# p8_led_matrix.net
KiCad netlist of a schematic drawn in Altium Designer
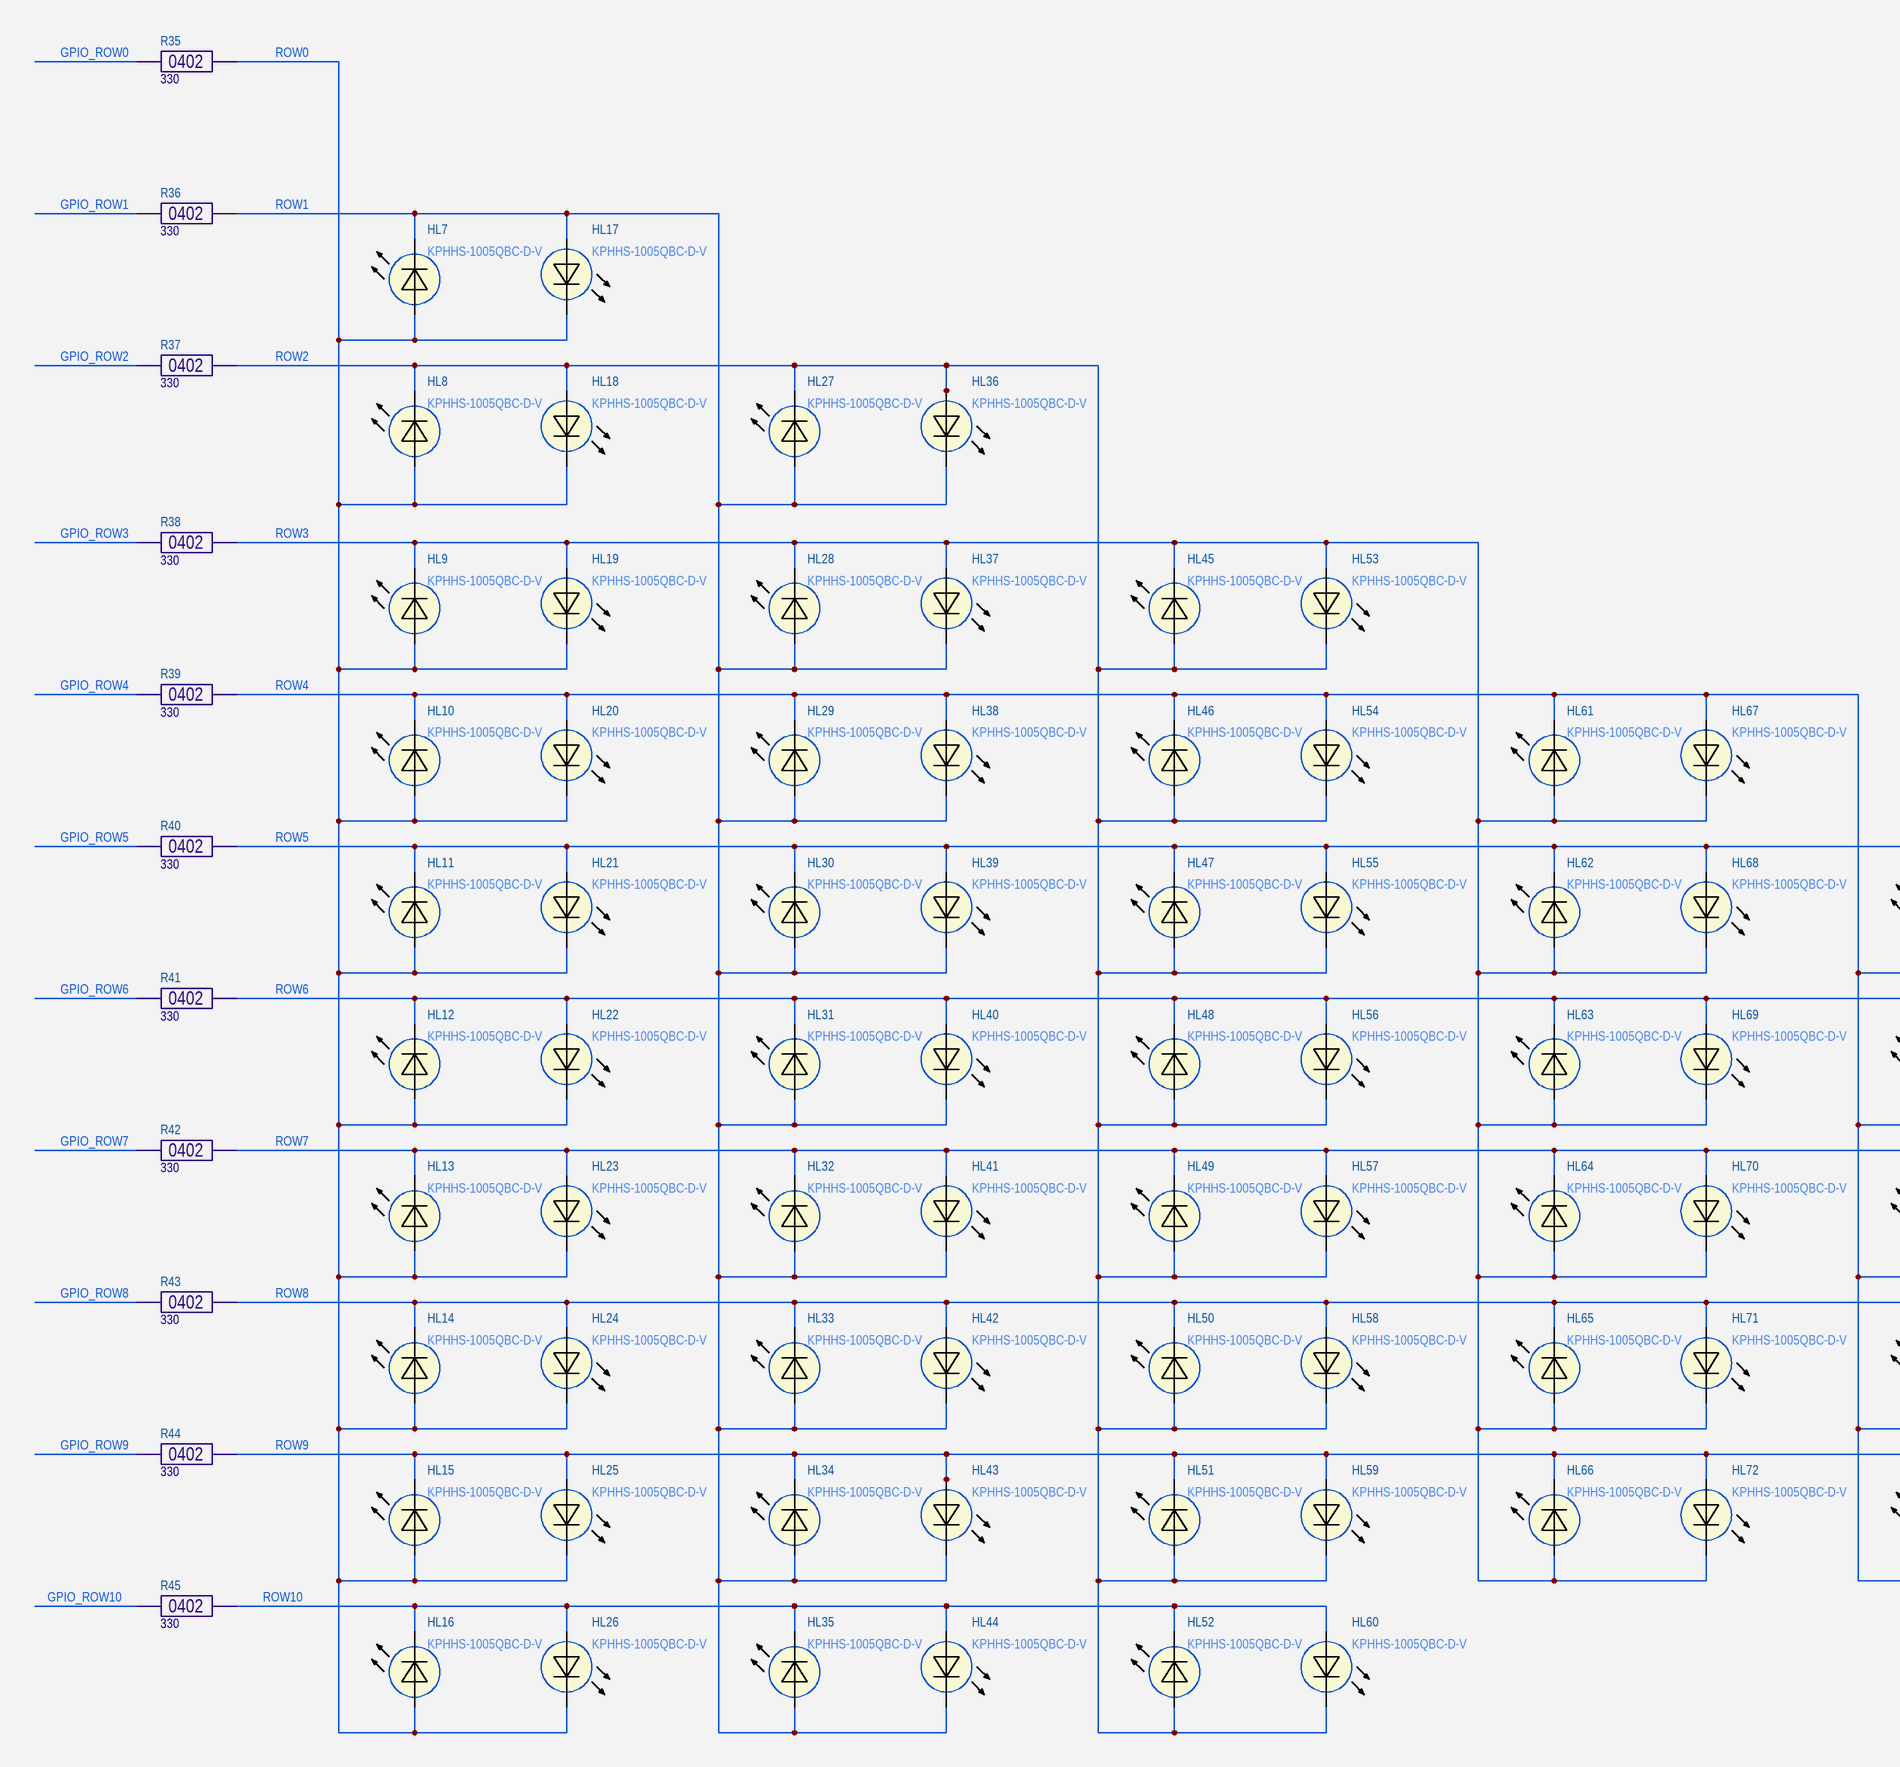
[diagram p0: p8_led_matrix.SchDoc, left]
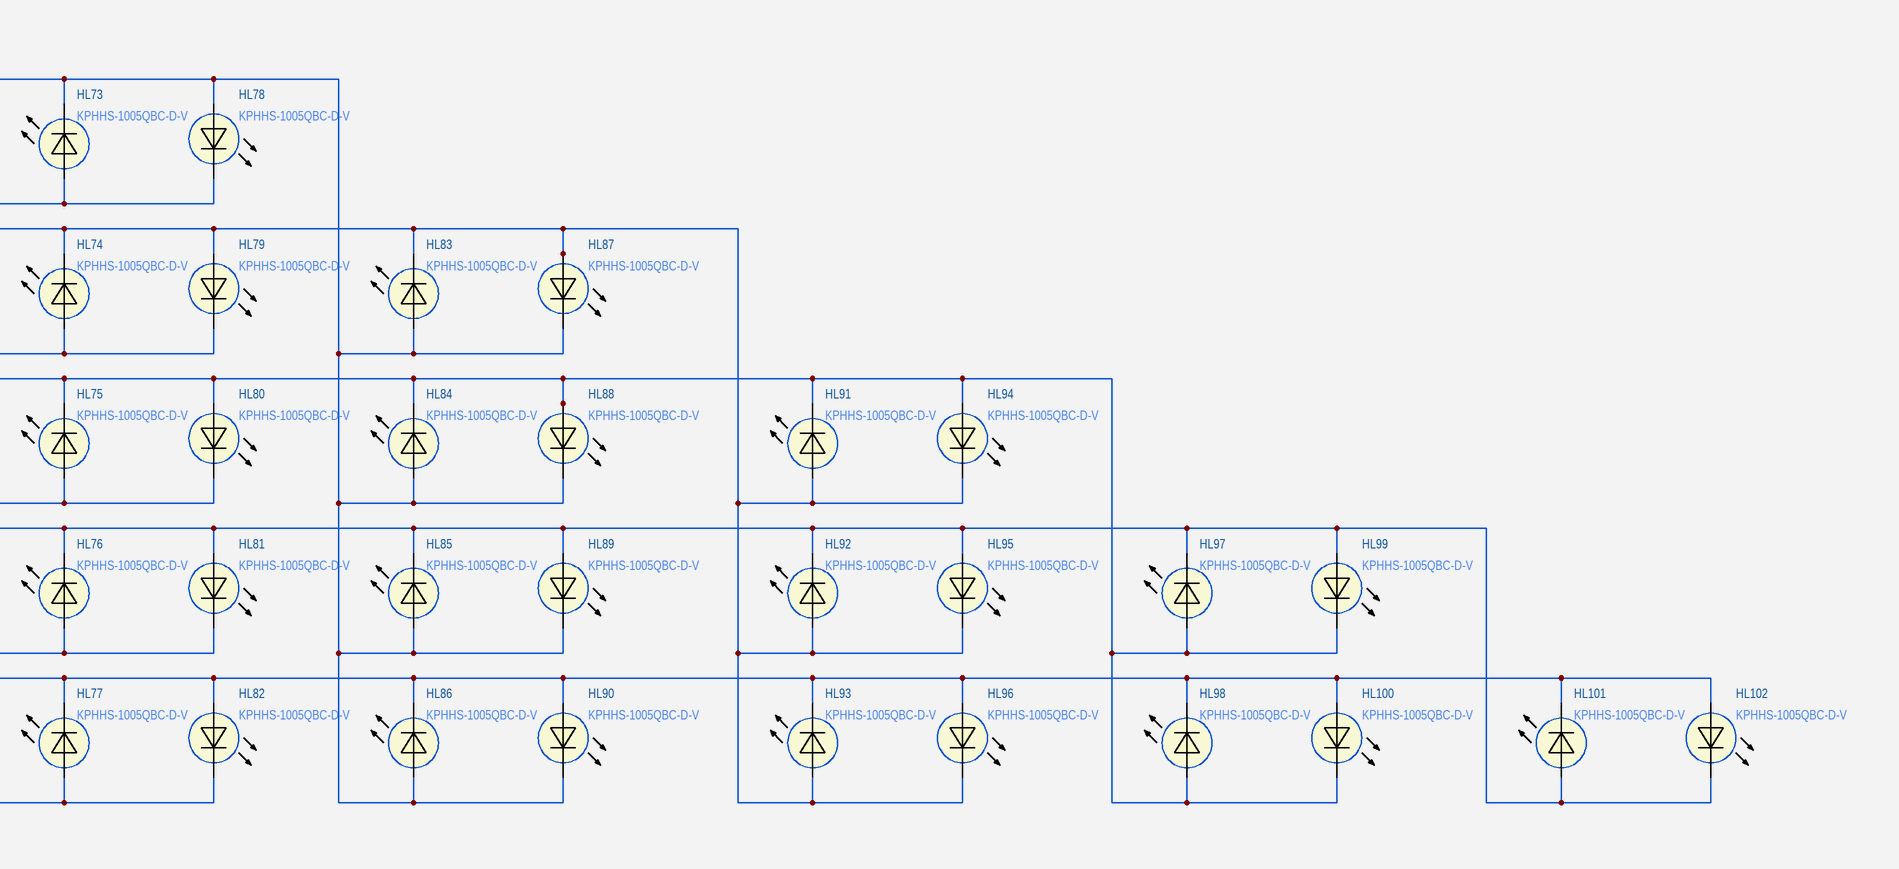
[diagram p1: p8_led_matrix.SchDoc, right]

(export (version "E")
  (design (tool "Eeschema 10.0.6"))
  (components
    (comp (ref "HL7")
      (value "KPHHS-1005QBC-D-V")
      (footprint "PcbLib_Others:LED0402B")
      (description "Blue led (package case 0402)")
      (fields (field (name "MANUFACTURER") "Kingbright Company LLC."))
      (libsource (lib "Schlib_Kingbright") (part "KPHHS-1005QBC-D-V"))
    )
    (comp (ref "HL8")
      (value "KPHHS-1005QBC-D-V")
      (footprint "PcbLib_Others:LED0402B")
      (description "Blue led (package case 0402)")
      (fields (field (name "MANUFACTURER") "Kingbright Company LLC."))
      (libsource (lib "Schlib_Kingbright") (part "KPHHS-1005QBC-D-V"))
    )
    (comp (ref "HL9")
      (value "KPHHS-1005QBC-D-V")
      (footprint "PcbLib_Others:LED0402B")
      (description "Blue led (package case 0402)")
      (fields (field (name "MANUFACTURER") "Kingbright Company LLC."))
      (libsource (lib "Schlib_Kingbright") (part "KPHHS-1005QBC-D-V"))
    )
    (comp (ref "HL10")
      (value "KPHHS-1005QBC-D-V")
      (footprint "PcbLib_Others:LED0402B")
      (description "Blue led (package case 0402)")
      (fields (field (name "MANUFACTURER") "Kingbright Company LLC."))
      (libsource (lib "Schlib_Kingbright") (part "KPHHS-1005QBC-D-V"))
    )
    (comp (ref "HL11")
      (value "KPHHS-1005QBC-D-V")
      (footprint "PcbLib_Others:LED0402B")
      (description "Blue led (package case 0402)")
      (fields (field (name "MANUFACTURER") "Kingbright Company LLC."))
      (libsource (lib "Schlib_Kingbright") (part "KPHHS-1005QBC-D-V"))
    )
    (comp (ref "HL12")
      (value "KPHHS-1005QBC-D-V")
      (footprint "PcbLib_Others:LED0402B")
      (description "Blue led (package case 0402)")
      (fields (field (name "MANUFACTURER") "Kingbright Company LLC."))
      (libsource (lib "Schlib_Kingbright") (part "KPHHS-1005QBC-D-V"))
    )
    (comp (ref "HL13")
      (value "KPHHS-1005QBC-D-V")
      (footprint "PcbLib_Others:LED0402B")
      (description "Blue led (package case 0402)")
      (fields (field (name "MANUFACTURER") "Kingbright Company LLC."))
      (libsource (lib "Schlib_Kingbright") (part "KPHHS-1005QBC-D-V"))
    )
    (comp (ref "HL14")
      (value "KPHHS-1005QBC-D-V")
      (footprint "PcbLib_Others:LED0402B")
      (description "Blue led (package case 0402)")
      (fields (field (name "MANUFACTURER") "Kingbright Company LLC."))
      (libsource (lib "Schlib_Kingbright") (part "KPHHS-1005QBC-D-V"))
    )
    (comp (ref "HL15")
      (value "KPHHS-1005QBC-D-V")
      (footprint "PcbLib_Others:LED0402B")
      (description "Blue led (package case 0402)")
      (fields (field (name "MANUFACTURER") "Kingbright Company LLC."))
      (libsource (lib "Schlib_Kingbright") (part "KPHHS-1005QBC-D-V"))
    )
    (comp (ref "HL16")
      (value "KPHHS-1005QBC-D-V")
      (footprint "PcbLib_Others:LED0402B")
      (description "Blue led (package case 0402)")
      (fields (field (name "MANUFACTURER") "Kingbright Company LLC."))
      (libsource (lib "Schlib_Kingbright") (part "KPHHS-1005QBC-D-V"))
    )
    (comp (ref "HL17")
      (value "KPHHS-1005QBC-D-V")
      (footprint "PcbLib_Others:LED0402B")
      (description "Blue led (package case 0402)")
      (fields (field (name "MANUFACTURER") "Kingbright Company LLC."))
      (libsource (lib "Schlib_Kingbright") (part "KPHHS-1005QBC-D-V"))
    )
    (comp (ref "HL18")
      (value "KPHHS-1005QBC-D-V")
      (footprint "PcbLib_Others:LED0402B")
      (description "Blue led (package case 0402)")
      (fields (field (name "MANUFACTURER") "Kingbright Company LLC."))
      (libsource (lib "Schlib_Kingbright") (part "KPHHS-1005QBC-D-V"))
    )
    (comp (ref "HL19")
      (value "KPHHS-1005QBC-D-V")
      (footprint "PcbLib_Others:LED0402B")
      (description "Blue led (package case 0402)")
      (fields (field (name "MANUFACTURER") "Kingbright Company LLC."))
      (libsource (lib "Schlib_Kingbright") (part "KPHHS-1005QBC-D-V"))
    )
    (comp (ref "HL20")
      (value "KPHHS-1005QBC-D-V")
      (footprint "PcbLib_Others:LED0402B")
      (description "Blue led (package case 0402)")
      (fields (field (name "MANUFACTURER") "Kingbright Company LLC."))
      (libsource (lib "Schlib_Kingbright") (part "KPHHS-1005QBC-D-V"))
    )
    (comp (ref "HL21")
      (value "KPHHS-1005QBC-D-V")
      (footprint "PcbLib_Others:LED0402B")
      (description "Blue led (package case 0402)")
      (fields (field (name "MANUFACTURER") "Kingbright Company LLC."))
      (libsource (lib "Schlib_Kingbright") (part "KPHHS-1005QBC-D-V"))
    )
    (comp (ref "HL22")
      (value "KPHHS-1005QBC-D-V")
      (footprint "PcbLib_Others:LED0402B")
      (description "Blue led (package case 0402)")
      (fields (field (name "MANUFACTURER") "Kingbright Company LLC."))
      (libsource (lib "Schlib_Kingbright") (part "KPHHS-1005QBC-D-V"))
    )
    (comp (ref "HL23")
      (value "KPHHS-1005QBC-D-V")
      (footprint "PcbLib_Others:LED0402B")
      (description "Blue led (package case 0402)")
      (fields (field (name "MANUFACTURER") "Kingbright Company LLC."))
      (libsource (lib "Schlib_Kingbright") (part "KPHHS-1005QBC-D-V"))
    )
    (comp (ref "HL24")
      (value "KPHHS-1005QBC-D-V")
      (footprint "PcbLib_Others:LED0402B")
      (description "Blue led (package case 0402)")
      (fields (field (name "MANUFACTURER") "Kingbright Company LLC."))
      (libsource (lib "Schlib_Kingbright") (part "KPHHS-1005QBC-D-V"))
    )
    (comp (ref "HL25")
      (value "KPHHS-1005QBC-D-V")
      (footprint "PcbLib_Others:LED0402B")
      (description "Blue led (package case 0402)")
      (fields (field (name "MANUFACTURER") "Kingbright Company LLC."))
      (libsource (lib "Schlib_Kingbright") (part "KPHHS-1005QBC-D-V"))
    )
    (comp (ref "HL26")
      (value "KPHHS-1005QBC-D-V")
      (footprint "PcbLib_Others:LED0402B")
      (description "Blue led (package case 0402)")
      (fields (field (name "MANUFACTURER") "Kingbright Company LLC."))
      (libsource (lib "Schlib_Kingbright") (part "KPHHS-1005QBC-D-V"))
    )
    (comp (ref "HL27")
      (value "KPHHS-1005QBC-D-V")
      (footprint "PcbLib_Others:LED0402B")
      (description "Blue led (package case 0402)")
      (fields (field (name "MANUFACTURER") "Kingbright Company LLC."))
      (libsource (lib "Schlib_Kingbright") (part "KPHHS-1005QBC-D-V"))
    )
    (comp (ref "HL28")
      (value "KPHHS-1005QBC-D-V")
      (footprint "PcbLib_Others:LED0402B")
      (description "Blue led (package case 0402)")
      (fields (field (name "MANUFACTURER") "Kingbright Company LLC."))
      (libsource (lib "Schlib_Kingbright") (part "KPHHS-1005QBC-D-V"))
    )
    (comp (ref "HL29")
      (value "KPHHS-1005QBC-D-V")
      (footprint "PcbLib_Others:LED0402B")
      (description "Blue led (package case 0402)")
      (fields (field (name "MANUFACTURER") "Kingbright Company LLC."))
      (libsource (lib "Schlib_Kingbright") (part "KPHHS-1005QBC-D-V"))
    )
    (comp (ref "HL30")
      (value "KPHHS-1005QBC-D-V")
      (footprint "PcbLib_Others:LED0402B")
      (description "Blue led (package case 0402)")
      (fields (field (name "MANUFACTURER") "Kingbright Company LLC."))
      (libsource (lib "Schlib_Kingbright") (part "KPHHS-1005QBC-D-V"))
    )
    (comp (ref "HL31")
      (value "KPHHS-1005QBC-D-V")
      (footprint "PcbLib_Others:LED0402B")
      (description "Blue led (package case 0402)")
      (fields (field (name "MANUFACTURER") "Kingbright Company LLC."))
      (libsource (lib "Schlib_Kingbright") (part "KPHHS-1005QBC-D-V"))
    )
    (comp (ref "HL32")
      (value "KPHHS-1005QBC-D-V")
      (footprint "PcbLib_Others:LED0402B")
      (description "Blue led (package case 0402)")
      (fields (field (name "MANUFACTURER") "Kingbright Company LLC."))
      (libsource (lib "Schlib_Kingbright") (part "KPHHS-1005QBC-D-V"))
    )
    (comp (ref "HL33")
      (value "KPHHS-1005QBC-D-V")
      (footprint "PcbLib_Others:LED0402B")
      (description "Blue led (package case 0402)")
      (fields (field (name "MANUFACTURER") "Kingbright Company LLC."))
      (libsource (lib "Schlib_Kingbright") (part "KPHHS-1005QBC-D-V"))
    )
    (comp (ref "HL34")
      (value "KPHHS-1005QBC-D-V")
      (footprint "PcbLib_Others:LED0402B")
      (description "Blue led (package case 0402)")
      (fields (field (name "MANUFACTURER") "Kingbright Company LLC."))
      (libsource (lib "Schlib_Kingbright") (part "KPHHS-1005QBC-D-V"))
    )
    (comp (ref "HL35")
      (value "KPHHS-1005QBC-D-V")
      (footprint "PcbLib_Others:LED0402B")
      (description "Blue led (package case 0402)")
      (fields (field (name "MANUFACTURER") "Kingbright Company LLC."))
      (libsource (lib "Schlib_Kingbright") (part "KPHHS-1005QBC-D-V"))
    )
    (comp (ref "HL36")
      (value "KPHHS-1005QBC-D-V")
      (footprint "PcbLib_Others:LED0402B")
      (description "Blue led (package case 0402)")
      (fields (field (name "MANUFACTURER") "Kingbright Company LLC."))
      (libsource (lib "Schlib_Kingbright") (part "KPHHS-1005QBC-D-V"))
    )
    (comp (ref "HL37")
      (value "KPHHS-1005QBC-D-V")
      (footprint "PcbLib_Others:LED0402B")
      (description "Blue led (package case 0402)")
      (fields (field (name "MANUFACTURER") "Kingbright Company LLC."))
      (libsource (lib "Schlib_Kingbright") (part "KPHHS-1005QBC-D-V"))
    )
    (comp (ref "HL38")
      (value "KPHHS-1005QBC-D-V")
      (footprint "PcbLib_Others:LED0402B")
      (description "Blue led (package case 0402)")
      (fields (field (name "MANUFACTURER") "Kingbright Company LLC."))
      (libsource (lib "Schlib_Kingbright") (part "KPHHS-1005QBC-D-V"))
    )
    (comp (ref "HL39")
      (value "KPHHS-1005QBC-D-V")
      (footprint "PcbLib_Others:LED0402B")
      (description "Blue led (package case 0402)")
      (fields (field (name "MANUFACTURER") "Kingbright Company LLC."))
      (libsource (lib "Schlib_Kingbright") (part "KPHHS-1005QBC-D-V"))
    )
    (comp (ref "HL40")
      (value "KPHHS-1005QBC-D-V")
      (footprint "PcbLib_Others:LED0402B")
      (description "Blue led (package case 0402)")
      (fields (field (name "MANUFACTURER") "Kingbright Company LLC."))
      (libsource (lib "Schlib_Kingbright") (part "KPHHS-1005QBC-D-V"))
    )
    (comp (ref "HL41")
      (value "KPHHS-1005QBC-D-V")
      (footprint "PcbLib_Others:LED0402B")
      (description "Blue led (package case 0402)")
      (fields (field (name "MANUFACTURER") "Kingbright Company LLC."))
      (libsource (lib "Schlib_Kingbright") (part "KPHHS-1005QBC-D-V"))
    )
    (comp (ref "HL42")
      (value "KPHHS-1005QBC-D-V")
      (footprint "PcbLib_Others:LED0402B")
      (description "Blue led (package case 0402)")
      (fields (field (name "MANUFACTURER") "Kingbright Company LLC."))
      (libsource (lib "Schlib_Kingbright") (part "KPHHS-1005QBC-D-V"))
    )
    (comp (ref "HL43")
      (value "KPHHS-1005QBC-D-V")
      (footprint "PcbLib_Others:LED0402B")
      (description "Blue led (package case 0402)")
      (fields (field (name "MANUFACTURER") "Kingbright Company LLC."))
      (libsource (lib "Schlib_Kingbright") (part "KPHHS-1005QBC-D-V"))
    )
    (comp (ref "HL44")
      (value "KPHHS-1005QBC-D-V")
      (footprint "PcbLib_Others:LED0402B")
      (description "Blue led (package case 0402)")
      (fields (field (name "MANUFACTURER") "Kingbright Company LLC."))
      (libsource (lib "Schlib_Kingbright") (part "KPHHS-1005QBC-D-V"))
    )
    (comp (ref "HL45")
      (value "KPHHS-1005QBC-D-V")
      (footprint "PcbLib_Others:LED0402B")
      (description "Blue led (package case 0402)")
      (fields (field (name "MANUFACTURER") "Kingbright Company LLC."))
      (libsource (lib "Schlib_Kingbright") (part "KPHHS-1005QBC-D-V"))
    )
    (comp (ref "HL46")
      (value "KPHHS-1005QBC-D-V")
      (footprint "PcbLib_Others:LED0402B")
      (description "Blue led (package case 0402)")
      (fields (field (name "MANUFACTURER") "Kingbright Company LLC."))
      (libsource (lib "Schlib_Kingbright") (part "KPHHS-1005QBC-D-V"))
    )
    (comp (ref "HL47")
      (value "KPHHS-1005QBC-D-V")
      (footprint "PcbLib_Others:LED0402B")
      (description "Blue led (package case 0402)")
      (fields (field (name "MANUFACTURER") "Kingbright Company LLC."))
      (libsource (lib "Schlib_Kingbright") (part "KPHHS-1005QBC-D-V"))
    )
    (comp (ref "HL48")
      (value "KPHHS-1005QBC-D-V")
      (footprint "PcbLib_Others:LED0402B")
      (description "Blue led (package case 0402)")
      (fields (field (name "MANUFACTURER") "Kingbright Company LLC."))
      (libsource (lib "Schlib_Kingbright") (part "KPHHS-1005QBC-D-V"))
    )
    (comp (ref "HL49")
      (value "KPHHS-1005QBC-D-V")
      (footprint "PcbLib_Others:LED0402B")
      (description "Blue led (package case 0402)")
      (fields (field (name "MANUFACTURER") "Kingbright Company LLC."))
      (libsource (lib "Schlib_Kingbright") (part "KPHHS-1005QBC-D-V"))
    )
    (comp (ref "HL50")
      (value "KPHHS-1005QBC-D-V")
      (footprint "PcbLib_Others:LED0402B")
      (description "Blue led (package case 0402)")
      (fields (field (name "MANUFACTURER") "Kingbright Company LLC."))
      (libsource (lib "Schlib_Kingbright") (part "KPHHS-1005QBC-D-V"))
    )
    (comp (ref "HL51")
      (value "KPHHS-1005QBC-D-V")
      (footprint "PcbLib_Others:LED0402B")
      (description "Blue led (package case 0402)")
      (fields (field (name "MANUFACTURER") "Kingbright Company LLC."))
      (libsource (lib "Schlib_Kingbright") (part "KPHHS-1005QBC-D-V"))
    )
    (comp (ref "HL52")
      (value "KPHHS-1005QBC-D-V")
      (footprint "PcbLib_Others:LED0402B")
      (description "Blue led (package case 0402)")
      (fields (field (name "MANUFACTURER") "Kingbright Company LLC."))
      (libsource (lib "Schlib_Kingbright") (part "KPHHS-1005QBC-D-V"))
    )
    (comp (ref "HL53")
      (value "KPHHS-1005QBC-D-V")
      (footprint "PcbLib_Others:LED0402B")
      (description "Blue led (package case 0402)")
      (fields (field (name "MANUFACTURER") "Kingbright Company LLC."))
      (libsource (lib "Schlib_Kingbright") (part "KPHHS-1005QBC-D-V"))
    )
    (comp (ref "HL54")
      (value "KPHHS-1005QBC-D-V")
      (footprint "PcbLib_Others:LED0402B")
      (description "Blue led (package case 0402)")
      (fields (field (name "MANUFACTURER") "Kingbright Company LLC."))
      (libsource (lib "Schlib_Kingbright") (part "KPHHS-1005QBC-D-V"))
    )
    (comp (ref "HL55")
      (value "KPHHS-1005QBC-D-V")
      (footprint "PcbLib_Others:LED0402B")
      (description "Blue led (package case 0402)")
      (fields (field (name "MANUFACTURER") "Kingbright Company LLC."))
      (libsource (lib "Schlib_Kingbright") (part "KPHHS-1005QBC-D-V"))
    )
    (comp (ref "HL56")
      (value "KPHHS-1005QBC-D-V")
      (footprint "PcbLib_Others:LED0402B")
      (description "Blue led (package case 0402)")
      (fields (field (name "MANUFACTURER") "Kingbright Company LLC."))
      (libsource (lib "Schlib_Kingbright") (part "KPHHS-1005QBC-D-V"))
    )
    (comp (ref "HL57")
      (value "KPHHS-1005QBC-D-V")
      (footprint "PcbLib_Others:LED0402B")
      (description "Blue led (package case 0402)")
      (fields (field (name "MANUFACTURER") "Kingbright Company LLC."))
      (libsource (lib "Schlib_Kingbright") (part "KPHHS-1005QBC-D-V"))
    )
    (comp (ref "HL58")
      (value "KPHHS-1005QBC-D-V")
      (footprint "PcbLib_Others:LED0402B")
      (description "Blue led (package case 0402)")
      (fields (field (name "MANUFACTURER") "Kingbright Company LLC."))
      (libsource (lib "Schlib_Kingbright") (part "KPHHS-1005QBC-D-V"))
    )
    (comp (ref "HL59")
      (value "KPHHS-1005QBC-D-V")
      (footprint "PcbLib_Others:LED0402B")
      (description "Blue led (package case 0402)")
      (fields (field (name "MANUFACTURER") "Kingbright Company LLC."))
      (libsource (lib "Schlib_Kingbright") (part "KPHHS-1005QBC-D-V"))
    )
    (comp (ref "HL60")
      (value "KPHHS-1005QBC-D-V")
      (footprint "PcbLib_Others:LED0402B")
      (description "Blue led (package case 0402)")
      (fields (field (name "MANUFACTURER") "Kingbright Company LLC."))
      (libsource (lib "Schlib_Kingbright") (part "KPHHS-1005QBC-D-V"))
    )
    (comp (ref "HL61")
      (value "KPHHS-1005QBC-D-V")
      (footprint "PcbLib_Others:LED0402B")
      (description "Blue led (package case 0402)")
      (fields (field (name "MANUFACTURER") "Kingbright Company LLC."))
      (libsource (lib "Schlib_Kingbright") (part "KPHHS-1005QBC-D-V"))
    )
    (comp (ref "HL62")
      (value "KPHHS-1005QBC-D-V")
      (footprint "PcbLib_Others:LED0402B")
      (description "Blue led (package case 0402)")
      (fields (field (name "MANUFACTURER") "Kingbright Company LLC."))
      (libsource (lib "Schlib_Kingbright") (part "KPHHS-1005QBC-D-V"))
    )
    (comp (ref "HL63")
      (value "KPHHS-1005QBC-D-V")
      (footprint "PcbLib_Others:LED0402B")
      (description "Blue led (package case 0402)")
      (fields (field (name "MANUFACTURER") "Kingbright Company LLC."))
      (libsource (lib "Schlib_Kingbright") (part "KPHHS-1005QBC-D-V"))
    )
    (comp (ref "HL64")
      (value "KPHHS-1005QBC-D-V")
      (footprint "PcbLib_Others:LED0402B")
      (description "Blue led (package case 0402)")
      (fields (field (name "MANUFACTURER") "Kingbright Company LLC."))
      (libsource (lib "Schlib_Kingbright") (part "KPHHS-1005QBC-D-V"))
    )
    (comp (ref "HL65")
      (value "KPHHS-1005QBC-D-V")
      (footprint "PcbLib_Others:LED0402B")
      (description "Blue led (package case 0402)")
      (fields (field (name "MANUFACTURER") "Kingbright Company LLC."))
      (libsource (lib "Schlib_Kingbright") (part "KPHHS-1005QBC-D-V"))
    )
    (comp (ref "HL66")
      (value "KPHHS-1005QBC-D-V")
      (footprint "PcbLib_Others:LED0402B")
      (description "Blue led (package case 0402)")
      (fields (field (name "MANUFACTURER") "Kingbright Company LLC."))
      (libsource (lib "Schlib_Kingbright") (part "KPHHS-1005QBC-D-V"))
    )
    (comp (ref "HL67")
      (value "KPHHS-1005QBC-D-V")
      (footprint "PcbLib_Others:LED0402B")
      (description "Blue led (package case 0402)")
      (fields (field (name "MANUFACTURER") "Kingbright Company LLC."))
      (libsource (lib "Schlib_Kingbright") (part "KPHHS-1005QBC-D-V"))
    )
    (comp (ref "HL68")
      (value "KPHHS-1005QBC-D-V")
      (footprint "PcbLib_Others:LED0402B")
      (description "Blue led (package case 0402)")
      (fields (field (name "MANUFACTURER") "Kingbright Company LLC."))
      (libsource (lib "Schlib_Kingbright") (part "KPHHS-1005QBC-D-V"))
    )
    (comp (ref "HL69")
      (value "KPHHS-1005QBC-D-V")
      (footprint "PcbLib_Others:LED0402B")
      (description "Blue led (package case 0402)")
      (fields (field (name "MANUFACTURER") "Kingbright Company LLC."))
      (libsource (lib "Schlib_Kingbright") (part "KPHHS-1005QBC-D-V"))
    )
    (comp (ref "HL70")
      (value "KPHHS-1005QBC-D-V")
      (footprint "PcbLib_Others:LED0402B")
      (description "Blue led (package case 0402)")
      (fields (field (name "MANUFACTURER") "Kingbright Company LLC."))
      (libsource (lib "Schlib_Kingbright") (part "KPHHS-1005QBC-D-V"))
    )
    (comp (ref "HL71")
      (value "KPHHS-1005QBC-D-V")
      (footprint "PcbLib_Others:LED0402B")
      (description "Blue led (package case 0402)")
      (fields (field (name "MANUFACTURER") "Kingbright Company LLC."))
      (libsource (lib "Schlib_Kingbright") (part "KPHHS-1005QBC-D-V"))
    )
    (comp (ref "HL72")
      (value "KPHHS-1005QBC-D-V")
      (footprint "PcbLib_Others:LED0402B")
      (description "Blue led (package case 0402)")
      (fields (field (name "MANUFACTURER") "Kingbright Company LLC."))
      (libsource (lib "Schlib_Kingbright") (part "KPHHS-1005QBC-D-V"))
    )
    (comp (ref "HL73")
      (value "KPHHS-1005QBC-D-V")
      (footprint "PcbLib_Others:LED0402B")
      (description "Blue led (package case 0402)")
      (fields (field (name "MANUFACTURER") "Kingbright Company LLC."))
      (libsource (lib "Schlib_Kingbright") (part "KPHHS-1005QBC-D-V"))
    )
    (comp (ref "HL74")
      (value "KPHHS-1005QBC-D-V")
      (footprint "PcbLib_Others:LED0402B")
      (description "Blue led (package case 0402)")
      (fields (field (name "MANUFACTURER") "Kingbright Company LLC."))
      (libsource (lib "Schlib_Kingbright") (part "KPHHS-1005QBC-D-V"))
    )
    (comp (ref "HL75")
      (value "KPHHS-1005QBC-D-V")
      (footprint "PcbLib_Others:LED0402B")
      (description "Blue led (package case 0402)")
      (fields (field (name "MANUFACTURER") "Kingbright Company LLC."))
      (libsource (lib "Schlib_Kingbright") (part "KPHHS-1005QBC-D-V"))
    )
    (comp (ref "HL76")
      (value "KPHHS-1005QBC-D-V")
      (footprint "PcbLib_Others:LED0402B")
      (description "Blue led (package case 0402)")
      (fields (field (name "MANUFACTURER") "Kingbright Company LLC."))
      (libsource (lib "Schlib_Kingbright") (part "KPHHS-1005QBC-D-V"))
    )
    (comp (ref "HL77")
      (value "KPHHS-1005QBC-D-V")
      (footprint "PcbLib_Others:LED0402B")
      (description "Blue led (package case 0402)")
      (fields (field (name "MANUFACTURER") "Kingbright Company LLC."))
      (libsource (lib "Schlib_Kingbright") (part "KPHHS-1005QBC-D-V"))
    )
    (comp (ref "HL78")
      (value "KPHHS-1005QBC-D-V")
      (footprint "PcbLib_Others:LED0402B")
      (description "Blue led (package case 0402)")
      (fields (field (name "MANUFACTURER") "Kingbright Company LLC."))
      (libsource (lib "Schlib_Kingbright") (part "KPHHS-1005QBC-D-V"))
    )
    (comp (ref "HL79")
      (value "KPHHS-1005QBC-D-V")
      (footprint "PcbLib_Others:LED0402B")
      (description "Blue led (package case 0402)")
      (fields (field (name "MANUFACTURER") "Kingbright Company LLC."))
      (libsource (lib "Schlib_Kingbright") (part "KPHHS-1005QBC-D-V"))
    )
    (comp (ref "HL80")
      (value "KPHHS-1005QBC-D-V")
      (footprint "PcbLib_Others:LED0402B")
      (description "Blue led (package case 0402)")
      (fields (field (name "MANUFACTURER") "Kingbright Company LLC."))
      (libsource (lib "Schlib_Kingbright") (part "KPHHS-1005QBC-D-V"))
    )
    (comp (ref "HL81")
      (value "KPHHS-1005QBC-D-V")
      (footprint "PcbLib_Others:LED0402B")
      (description "Blue led (package case 0402)")
      (fields (field (name "MANUFACTURER") "Kingbright Company LLC."))
      (libsource (lib "Schlib_Kingbright") (part "KPHHS-1005QBC-D-V"))
    )
    (comp (ref "HL82")
      (value "KPHHS-1005QBC-D-V")
      (footprint "PcbLib_Others:LED0402B")
      (description "Blue led (package case 0402)")
      (fields (field (name "MANUFACTURER") "Kingbright Company LLC."))
      (libsource (lib "Schlib_Kingbright") (part "KPHHS-1005QBC-D-V"))
    )
    (comp (ref "HL83")
      (value "KPHHS-1005QBC-D-V")
      (footprint "PcbLib_Others:LED0402B")
      (description "Blue led (package case 0402)")
      (fields (field (name "MANUFACTURER") "Kingbright Company LLC."))
      (libsource (lib "Schlib_Kingbright") (part "KPHHS-1005QBC-D-V"))
    )
    (comp (ref "HL84")
      (value "KPHHS-1005QBC-D-V")
      (footprint "PcbLib_Others:LED0402B")
      (description "Blue led (package case 0402)")
      (fields (field (name "MANUFACTURER") "Kingbright Company LLC."))
      (libsource (lib "Schlib_Kingbright") (part "KPHHS-1005QBC-D-V"))
    )
    (comp (ref "HL85")
      (value "KPHHS-1005QBC-D-V")
      (footprint "PcbLib_Others:LED0402B")
      (description "Blue led (package case 0402)")
      (fields (field (name "MANUFACTURER") "Kingbright Company LLC."))
      (libsource (lib "Schlib_Kingbright") (part "KPHHS-1005QBC-D-V"))
    )
    (comp (ref "HL86")
      (value "KPHHS-1005QBC-D-V")
      (footprint "PcbLib_Others:LED0402B")
      (description "Blue led (package case 0402)")
      (fields (field (name "MANUFACTURER") "Kingbright Company LLC."))
      (libsource (lib "Schlib_Kingbright") (part "KPHHS-1005QBC-D-V"))
    )
    (comp (ref "HL87")
      (value "KPHHS-1005QBC-D-V")
      (footprint "PcbLib_Others:LED0402B")
      (description "Blue led (package case 0402)")
      (fields (field (name "MANUFACTURER") "Kingbright Company LLC."))
      (libsource (lib "Schlib_Kingbright") (part "KPHHS-1005QBC-D-V"))
    )
    (comp (ref "HL88")
      (value "KPHHS-1005QBC-D-V")
      (footprint "PcbLib_Others:LED0402B")
      (description "Blue led (package case 0402)")
      (fields (field (name "MANUFACTURER") "Kingbright Company LLC."))
      (libsource (lib "Schlib_Kingbright") (part "KPHHS-1005QBC-D-V"))
    )
    (comp (ref "HL89")
      (value "KPHHS-1005QBC-D-V")
      (footprint "PcbLib_Others:LED0402B")
      (description "Blue led (package case 0402)")
      (fields (field (name "MANUFACTURER") "Kingbright Company LLC."))
      (libsource (lib "Schlib_Kingbright") (part "KPHHS-1005QBC-D-V"))
    )
    (comp (ref "HL90")
      (value "KPHHS-1005QBC-D-V")
      (footprint "PcbLib_Others:LED0402B")
      (description "Blue led (package case 0402)")
      (fields (field (name "MANUFACTURER") "Kingbright Company LLC."))
      (libsource (lib "Schlib_Kingbright") (part "KPHHS-1005QBC-D-V"))
    )
    (comp (ref "HL91")
      (value "KPHHS-1005QBC-D-V")
      (footprint "PcbLib_Others:LED0402B")
      (description "Blue led (package case 0402)")
      (fields (field (name "MANUFACTURER") "Kingbright Company LLC."))
      (libsource (lib "Schlib_Kingbright") (part "KPHHS-1005QBC-D-V"))
    )
    (comp (ref "HL92")
      (value "KPHHS-1005QBC-D-V")
      (footprint "PcbLib_Others:LED0402B")
      (description "Blue led (package case 0402)")
      (fields (field (name "MANUFACTURER") "Kingbright Company LLC."))
      (libsource (lib "Schlib_Kingbright") (part "KPHHS-1005QBC-D-V"))
    )
    (comp (ref "HL93")
      (value "KPHHS-1005QBC-D-V")
      (footprint "PcbLib_Others:LED0402B")
      (description "Blue led (package case 0402)")
      (fields (field (name "MANUFACTURER") "Kingbright Company LLC."))
      (libsource (lib "Schlib_Kingbright") (part "KPHHS-1005QBC-D-V"))
    )
    (comp (ref "HL94")
      (value "KPHHS-1005QBC-D-V")
      (footprint "PcbLib_Others:LED0402B")
      (description "Blue led (package case 0402)")
      (fields (field (name "MANUFACTURER") "Kingbright Company LLC."))
      (libsource (lib "Schlib_Kingbright") (part "KPHHS-1005QBC-D-V"))
    )
    (comp (ref "HL95")
      (value "KPHHS-1005QBC-D-V")
      (footprint "PcbLib_Others:LED0402B")
      (description "Blue led (package case 0402)")
      (fields (field (name "MANUFACTURER") "Kingbright Company LLC."))
      (libsource (lib "Schlib_Kingbright") (part "KPHHS-1005QBC-D-V"))
    )
    (comp (ref "HL96")
      (value "KPHHS-1005QBC-D-V")
      (footprint "PcbLib_Others:LED0402B")
      (description "Blue led (package case 0402)")
      (fields (field (name "MANUFACTURER") "Kingbright Company LLC."))
      (libsource (lib "Schlib_Kingbright") (part "KPHHS-1005QBC-D-V"))
    )
    (comp (ref "HL97")
      (value "KPHHS-1005QBC-D-V")
      (footprint "PcbLib_Others:LED0402B")
      (description "Blue led (package case 0402)")
      (fields (field (name "MANUFACTURER") "Kingbright Company LLC."))
      (libsource (lib "Schlib_Kingbright") (part "KPHHS-1005QBC-D-V"))
    )
    (comp (ref "HL98")
      (value "KPHHS-1005QBC-D-V")
      (footprint "PcbLib_Others:LED0402B")
      (description "Blue led (package case 0402)")
      (fields (field (name "MANUFACTURER") "Kingbright Company LLC."))
      (libsource (lib "Schlib_Kingbright") (part "KPHHS-1005QBC-D-V"))
    )
    (comp (ref "HL99")
      (value "KPHHS-1005QBC-D-V")
      (footprint "PcbLib_Others:LED0402B")
      (description "Blue led (package case 0402)")
      (fields (field (name "MANUFACTURER") "Kingbright Company LLC."))
      (libsource (lib "Schlib_Kingbright") (part "KPHHS-1005QBC-D-V"))
    )
    (comp (ref "HL100")
      (value "KPHHS-1005QBC-D-V")
      (footprint "PcbLib_Others:LED0402B")
      (description "Blue led (package case 0402)")
      (fields (field (name "MANUFACTURER") "Kingbright Company LLC."))
      (libsource (lib "Schlib_Kingbright") (part "KPHHS-1005QBC-D-V"))
    )
    (comp (ref "HL101")
      (value "KPHHS-1005QBC-D-V")
      (footprint "PcbLib_Others:LED0402B")
      (description "Blue led (package case 0402)")
      (fields (field (name "MANUFACTURER") "Kingbright Company LLC."))
      (libsource (lib "Schlib_Kingbright") (part "KPHHS-1005QBC-D-V"))
    )
    (comp (ref "HL102")
      (value "KPHHS-1005QBC-D-V")
      (footprint "PcbLib_Others:LED0402B")
      (description "Blue led (package case 0402)")
      (fields (field (name "MANUFACTURER") "Kingbright Company LLC."))
      (libsource (lib "Schlib_Kingbright") (part "KPHHS-1005QBC-D-V"))
    )
    (comp (ref "R35")
      (value "330")
      (footprint "PcbLib_RC:RES0402B")
      (description "Resistor 0402 package case")
      (fields
        (field (name "TOLERANCE") "± 1 %")
        (field (name "PART NUMBER") "RC0402FR-07330RL")
        (field (name "PACKAGE") "0402")
      )
      (libsource (lib "Schlib_RC") (part "R0402"))
    )
    (comp (ref "R36")
      (value "330")
      (footprint "PcbLib_RC:RES0402B")
      (description "Resistor 0402 package case")
      (fields
        (field (name "TOLERANCE") "± 1 %")
        (field (name "PART NUMBER") "RC0402FR-07330RL")
        (field (name "PACKAGE") "0402")
      )
      (libsource (lib "Schlib_RC") (part "R0402"))
    )
    (comp (ref "R37")
      (value "330")
      (footprint "PcbLib_RC:RES0402B")
      (description "Resistor 0402 package case")
      (fields
        (field (name "TOLERANCE") "± 1 %")
        (field (name "PART NUMBER") "RC0402FR-07330RL")
        (field (name "PACKAGE") "0402")
      )
      (libsource (lib "Schlib_RC") (part "R0402"))
    )
    (comp (ref "R38")
      (value "330")
      (footprint "PcbLib_RC:RES0402B")
      (description "Resistor 0402 package case")
      (fields
        (field (name "TOLERANCE") "± 1 %")
        (field (name "PART NUMBER") "RC0402FR-07330RL")
        (field (name "PACKAGE") "0402")
      )
      (libsource (lib "Schlib_RC") (part "R0402"))
    )
    (comp (ref "R39")
      (value "330")
      (footprint "PcbLib_RC:RES0402B")
      (description "Resistor 0402 package case")
      (fields
        (field (name "TOLERANCE") "± 1 %")
        (field (name "PART NUMBER") "RC0402FR-07330RL")
        (field (name "PACKAGE") "0402")
      )
      (libsource (lib "Schlib_RC") (part "R0402"))
    )
    (comp (ref "R40")
      (value "330")
      (footprint "PcbLib_RC:RES0402B")
      (description "Resistor 0402 package case")
      (fields
        (field (name "TOLERANCE") "± 1 %")
        (field (name "PART NUMBER") "RC0402FR-07330RL")
        (field (name "PACKAGE") "0402")
      )
      (libsource (lib "Schlib_RC") (part "R0402"))
    )
    (comp (ref "R41")
      (value "330")
      (footprint "PcbLib_RC:RES0402B")
      (description "Resistor 0402 package case")
      (fields
        (field (name "TOLERANCE") "± 1 %")
        (field (name "PART NUMBER") "RC0402FR-07330RL")
        (field (name "PACKAGE") "0402")
      )
      (libsource (lib "Schlib_RC") (part "R0402"))
    )
    (comp (ref "R42")
      (value "330")
      (footprint "PcbLib_RC:RES0402B")
      (description "Resistor 0402 package case")
      (fields
        (field (name "TOLERANCE") "± 1 %")
        (field (name "PART NUMBER") "RC0402FR-07330RL")
        (field (name "PACKAGE") "0402")
      )
      (libsource (lib "Schlib_RC") (part "R0402"))
    )
    (comp (ref "R43")
      (value "330")
      (footprint "PcbLib_RC:RES0402B")
      (description "Resistor 0402 package case")
      (fields
        (field (name "TOLERANCE") "± 1 %")
        (field (name "PART NUMBER") "RC0402FR-07330RL")
        (field (name "PACKAGE") "0402")
      )
      (libsource (lib "Schlib_RC") (part "R0402"))
    )
    (comp (ref "R44")
      (value "330")
      (footprint "PcbLib_RC:RES0402B")
      (description "Resistor 0402 package case")
      (fields
        (field (name "TOLERANCE") "± 1 %")
        (field (name "PART NUMBER") "RC0402FR-07330RL")
        (field (name "PACKAGE") "0402")
      )
      (libsource (lib "Schlib_RC") (part "R0402"))
    )
    (comp (ref "R45")
      (value "330")
      (footprint "PcbLib_RC:RES0402B")
      (description "Resistor 0402 package case")
      (fields
        (field (name "TOLERANCE") "± 1 %")
        (field (name "PART NUMBER") "RC0402FR-07330RL")
        (field (name "PACKAGE") "0402")
      )
      (libsource (lib "Schlib_RC") (part "R0402"))
    )
  )
  (nets
    (net (code "1") (name "/GPIO_ROW0") (class "Default")
      (node (ref "R35") (pin "2") (pinfunction "2_2") (pintype "passive"))
    )
    (net (code "2") (name "/GPIO_ROW1") (class "Default")
      (node (ref "R36") (pin "2") (pinfunction "2_2") (pintype "passive"))
    )
    (net (code "3") (name "/GPIO_ROW2") (class "Default")
      (node (ref "R37") (pin "2") (pinfunction "2_2") (pintype "passive"))
    )
    (net (code "4") (name "/GPIO_ROW3") (class "Default")
      (node (ref "R38") (pin "2") (pinfunction "2_2") (pintype "passive"))
    )
    (net (code "5") (name "/GPIO_ROW4") (class "Default")
      (node (ref "R39") (pin "2") (pinfunction "2_2") (pintype "passive"))
    )
    (net (code "6") (name "/GPIO_ROW5") (class "Default")
      (node (ref "R40") (pin "2") (pinfunction "2_2") (pintype "passive"))
    )
    (net (code "7") (name "/GPIO_ROW6") (class "Default")
      (node (ref "R41") (pin "2") (pinfunction "2_2") (pintype "passive"))
    )
    (net (code "8") (name "/GPIO_ROW7") (class "Default")
      (node (ref "R42") (pin "2") (pinfunction "2_2") (pintype "passive"))
    )
    (net (code "9") (name "/GPIO_ROW8") (class "Default")
      (node (ref "R43") (pin "2") (pinfunction "2_2") (pintype "passive"))
    )
    (net (code "10") (name "/GPIO_ROW9") (class "Default")
      (node (ref "R44") (pin "2") (pinfunction "2_2") (pintype "passive"))
    )
    (net (code "11") (name "/GPIO_ROW10") (class "Default")
      (node (ref "R45") (pin "2") (pinfunction "2_2") (pintype "passive"))
    )
    (net (code "12") (name "/ROW0") (class "Default")
      (node (ref "HL10") (pin "2") (pinfunction "2_2") (pintype "passive"))
      (node (ref "HL11") (pin "2") (pinfunction "2_2") (pintype "passive"))
      (node (ref "HL12") (pin "2") (pinfunction "2_2") (pintype "passive"))
      (node (ref "HL13") (pin "2") (pinfunction "2_2") (pintype "passive"))
      (node (ref "HL14") (pin "2") (pinfunction "2_2") (pintype "passive"))
      (node (ref "HL15") (pin "2") (pinfunction "2_2") (pintype "passive"))
      (node (ref "HL16") (pin "2") (pinfunction "2_2") (pintype "passive"))
      (node (ref "HL17") (pin "1") (pinfunction "1_1") (pintype "passive"))
      (node (ref "HL18") (pin "1") (pinfunction "1_1") (pintype "passive"))
      (node (ref "HL19") (pin "1") (pinfunction "1_1") (pintype "passive"))
      (node (ref "HL20") (pin "1") (pinfunction "1_1") (pintype "passive"))
      (node (ref "HL21") (pin "1") (pinfunction "1_1") (pintype "passive"))
      (node (ref "HL22") (pin "1") (pinfunction "1_1") (pintype "passive"))
      (node (ref "HL23") (pin "1") (pinfunction "1_1") (pintype "passive"))
      (node (ref "HL24") (pin "1") (pinfunction "1_1") (pintype "passive"))
      (node (ref "HL25") (pin "1") (pinfunction "1_1") (pintype "passive"))
      (node (ref "HL26") (pin "1") (pinfunction "1_1") (pintype "passive"))
      (node (ref "HL7") (pin "2") (pinfunction "2_2") (pintype "passive"))
      (node (ref "HL8") (pin "2") (pinfunction "2_2") (pintype "passive"))
      (node (ref "HL9") (pin "2") (pinfunction "2_2") (pintype "passive"))
      (node (ref "R35") (pin "1") (pinfunction "1_1") (pintype "passive"))
    )
    (net (code "13") (name "/ROW1") (class "Default")
      (node (ref "HL17") (pin "2") (pinfunction "2_2") (pintype "passive"))
      (node (ref "HL27") (pin "2") (pinfunction "2_2") (pintype "passive"))
      (node (ref "HL28") (pin "2") (pinfunction "2_2") (pintype "passive"))
      (node (ref "HL29") (pin "2") (pinfunction "2_2") (pintype "passive"))
      (node (ref "HL30") (pin "2") (pinfunction "2_2") (pintype "passive"))
      (node (ref "HL31") (pin "2") (pinfunction "2_2") (pintype "passive"))
      (node (ref "HL32") (pin "2") (pinfunction "2_2") (pintype "passive"))
      (node (ref "HL33") (pin "2") (pinfunction "2_2") (pintype "passive"))
      (node (ref "HL34") (pin "2") (pinfunction "2_2") (pintype "passive"))
      (node (ref "HL35") (pin "2") (pinfunction "2_2") (pintype "passive"))
      (node (ref "HL36") (pin "1") (pinfunction "1_1") (pintype "passive"))
      (node (ref "HL37") (pin "1") (pinfunction "1_1") (pintype "passive"))
      (node (ref "HL38") (pin "1") (pinfunction "1_1") (pintype "passive"))
      (node (ref "HL39") (pin "1") (pinfunction "1_1") (pintype "passive"))
      (node (ref "HL40") (pin "1") (pinfunction "1_1") (pintype "passive"))
      (node (ref "HL41") (pin "1") (pinfunction "1_1") (pintype "passive"))
      (node (ref "HL42") (pin "1") (pinfunction "1_1") (pintype "passive"))
      (node (ref "HL43") (pin "1") (pinfunction "1_1") (pintype "passive"))
      (node (ref "HL44") (pin "1") (pinfunction "1_1") (pintype "passive"))
      (node (ref "HL7") (pin "1") (pinfunction "1_1") (pintype "passive"))
      (node (ref "R36") (pin "1") (pinfunction "1_1") (pintype "passive"))
    )
    (net (code "14") (name "/ROW2") (class "Default")
      (node (ref "HL18") (pin "2") (pinfunction "2_2") (pintype "passive"))
      (node (ref "HL27") (pin "1") (pinfunction "1_1") (pintype "passive"))
      (node (ref "HL36") (pin "2") (pinfunction "2_2") (pintype "passive"))
      (node (ref "HL45") (pin "2") (pinfunction "2_2") (pintype "passive"))
      (node (ref "HL46") (pin "2") (pinfunction "2_2") (pintype "passive"))
      (node (ref "HL47") (pin "2") (pinfunction "2_2") (pintype "passive"))
      (node (ref "HL48") (pin "2") (pinfunction "2_2") (pintype "passive"))
      (node (ref "HL49") (pin "2") (pinfunction "2_2") (pintype "passive"))
      (node (ref "HL50") (pin "2") (pinfunction "2_2") (pintype "passive"))
      (node (ref "HL51") (pin "2") (pinfunction "2_2") (pintype "passive"))
      (node (ref "HL52") (pin "2") (pinfunction "2_2") (pintype "passive"))
      (node (ref "HL53") (pin "1") (pinfunction "1_1") (pintype "passive"))
      (node (ref "HL54") (pin "1") (pinfunction "1_1") (pintype "passive"))
      (node (ref "HL55") (pin "1") (pinfunction "1_1") (pintype "passive"))
      (node (ref "HL56") (pin "1") (pinfunction "1_1") (pintype "passive"))
      (node (ref "HL57") (pin "1") (pinfunction "1_1") (pintype "passive"))
      (node (ref "HL58") (pin "1") (pinfunction "1_1") (pintype "passive"))
      (node (ref "HL59") (pin "1") (pinfunction "1_1") (pintype "passive"))
      (node (ref "HL60") (pin "1") (pinfunction "1_1") (pintype "passive"))
      (node (ref "HL8") (pin "1") (pinfunction "1_1") (pintype "passive"))
      (node (ref "R37") (pin "1") (pinfunction "1_1") (pintype "passive"))
    )
    (net (code "15") (name "/ROW3") (class "Default")
      (node (ref "HL19") (pin "2") (pinfunction "2_2") (pintype "passive"))
      (node (ref "HL28") (pin "1") (pinfunction "1_1") (pintype "passive"))
      (node (ref "HL37") (pin "2") (pinfunction "2_2") (pintype "passive"))
      (node (ref "HL45") (pin "1") (pinfunction "1_1") (pintype "passive"))
      (node (ref "HL53") (pin "2") (pinfunction "2_2") (pintype "passive"))
      (node (ref "HL61") (pin "2") (pinfunction "2_2") (pintype "passive"))
      (node (ref "HL62") (pin "2") (pinfunction "2_2") (pintype "passive"))
      (node (ref "HL63") (pin "2") (pinfunction "2_2") (pintype "passive"))
      (node (ref "HL64") (pin "2") (pinfunction "2_2") (pintype "passive"))
      (node (ref "HL65") (pin "2") (pinfunction "2_2") (pintype "passive"))
      (node (ref "HL66") (pin "2") (pinfunction "2_2") (pintype "passive"))
      (node (ref "HL67") (pin "1") (pinfunction "1_1") (pintype "passive"))
      (node (ref "HL68") (pin "1") (pinfunction "1_1") (pintype "passive"))
      (node (ref "HL69") (pin "1") (pinfunction "1_1") (pintype "passive"))
      (node (ref "HL70") (pin "1") (pinfunction "1_1") (pintype "passive"))
      (node (ref "HL71") (pin "1") (pinfunction "1_1") (pintype "passive"))
      (node (ref "HL72") (pin "1") (pinfunction "1_1") (pintype "passive"))
      (node (ref "HL9") (pin "1") (pinfunction "1_1") (pintype "passive"))
      (node (ref "R38") (pin "1") (pinfunction "1_1") (pintype "passive"))
    )
    (net (code "16") (name "/ROW4") (class "Default")
      (node (ref "HL10") (pin "1") (pinfunction "1_1") (pintype "passive"))
      (node (ref "HL20") (pin "2") (pinfunction "2_2") (pintype "passive"))
      (node (ref "HL29") (pin "1") (pinfunction "1_1") (pintype "passive"))
      (node (ref "HL38") (pin "2") (pinfunction "2_2") (pintype "passive"))
      (node (ref "HL46") (pin "1") (pinfunction "1_1") (pintype "passive"))
      (node (ref "HL54") (pin "2") (pinfunction "2_2") (pintype "passive"))
      (node (ref "HL61") (pin "1") (pinfunction "1_1") (pintype "passive"))
      (node (ref "HL67") (pin "2") (pinfunction "2_2") (pintype "passive"))
      (node (ref "HL73") (pin "2") (pinfunction "2_2") (pintype "passive"))
      (node (ref "HL74") (pin "2") (pinfunction "2_2") (pintype "passive"))
      (node (ref "HL75") (pin "2") (pinfunction "2_2") (pintype "passive"))
      (node (ref "HL76") (pin "2") (pinfunction "2_2") (pintype "passive"))
      (node (ref "HL77") (pin "2") (pinfunction "2_2") (pintype "passive"))
      (node (ref "HL78") (pin "1") (pinfunction "1_1") (pintype "passive"))
      (node (ref "HL79") (pin "1") (pinfunction "1_1") (pintype "passive"))
      (node (ref "HL80") (pin "1") (pinfunction "1_1") (pintype "passive"))
      (node (ref "HL81") (pin "1") (pinfunction "1_1") (pintype "passive"))
      (node (ref "HL82") (pin "1") (pinfunction "1_1") (pintype "passive"))
      (node (ref "R39") (pin "1") (pinfunction "1_1") (pintype "passive"))
    )
    (net (code "17") (name "/ROW5") (class "Default")
      (node (ref "HL11") (pin "1") (pinfunction "1_1") (pintype "passive"))
      (node (ref "HL21") (pin "2") (pinfunction "2_2") (pintype "passive"))
      (node (ref "HL30") (pin "1") (pinfunction "1_1") (pintype "passive"))
      (node (ref "HL39") (pin "2") (pinfunction "2_2") (pintype "passive"))
      (node (ref "HL47") (pin "1") (pinfunction "1_1") (pintype "passive"))
      (node (ref "HL55") (pin "2") (pinfunction "2_2") (pintype "passive"))
      (node (ref "HL62") (pin "1") (pinfunction "1_1") (pintype "passive"))
      (node (ref "HL68") (pin "2") (pinfunction "2_2") (pintype "passive"))
      (node (ref "HL73") (pin "1") (pinfunction "1_1") (pintype "passive"))
      (node (ref "HL78") (pin "2") (pinfunction "2_2") (pintype "passive"))
      (node (ref "HL83") (pin "2") (pinfunction "2_2") (pintype "passive"))
      (node (ref "HL84") (pin "2") (pinfunction "2_2") (pintype "passive"))
      (node (ref "HL85") (pin "2") (pinfunction "2_2") (pintype "passive"))
      (node (ref "HL86") (pin "2") (pinfunction "2_2") (pintype "passive"))
      (node (ref "HL87") (pin "1") (pinfunction "1_1") (pintype "passive"))
      (node (ref "HL88") (pin "1") (pinfunction "1_1") (pintype "passive"))
      (node (ref "HL89") (pin "1") (pinfunction "1_1") (pintype "passive"))
      (node (ref "HL90") (pin "1") (pinfunction "1_1") (pintype "passive"))
      (node (ref "R40") (pin "1") (pinfunction "1_1") (pintype "passive"))
    )
    (net (code "18") (name "/ROW6") (class "Default")
      (node (ref "HL12") (pin "1") (pinfunction "1_1") (pintype "passive"))
      (node (ref "HL22") (pin "2") (pinfunction "2_2") (pintype "passive"))
      (node (ref "HL31") (pin "1") (pinfunction "1_1") (pintype "passive"))
      (node (ref "HL40") (pin "2") (pinfunction "2_2") (pintype "passive"))
      (node (ref "HL48") (pin "1") (pinfunction "1_1") (pintype "passive"))
      (node (ref "HL56") (pin "2") (pinfunction "2_2") (pintype "passive"))
      (node (ref "HL63") (pin "1") (pinfunction "1_1") (pintype "passive"))
      (node (ref "HL69") (pin "2") (pinfunction "2_2") (pintype "passive"))
      (node (ref "HL74") (pin "1") (pinfunction "1_1") (pintype "passive"))
      (node (ref "HL79") (pin "2") (pinfunction "2_2") (pintype "passive"))
      (node (ref "HL83") (pin "1") (pinfunction "1_1") (pintype "passive"))
      (node (ref "HL87") (pin "2") (pinfunction "2_2") (pintype "passive"))
      (node (ref "HL91") (pin "2") (pinfunction "2_2") (pintype "passive"))
      (node (ref "HL92") (pin "2") (pinfunction "2_2") (pintype "passive"))
      (node (ref "HL93") (pin "2") (pinfunction "2_2") (pintype "passive"))
      (node (ref "HL94") (pin "1") (pinfunction "1_1") (pintype "passive"))
      (node (ref "HL95") (pin "1") (pinfunction "1_1") (pintype "passive"))
      (node (ref "HL96") (pin "1") (pinfunction "1_1") (pintype "passive"))
      (node (ref "R41") (pin "1") (pinfunction "1_1") (pintype "passive"))
    )
    (net (code "19") (name "/ROW7") (class "Default")
      (node (ref "HL100") (pin "1") (pinfunction "1_1") (pintype "passive"))
      (node (ref "HL13") (pin "1") (pinfunction "1_1") (pintype "passive"))
      (node (ref "HL23") (pin "2") (pinfunction "2_2") (pintype "passive"))
      (node (ref "HL32") (pin "1") (pinfunction "1_1") (pintype "passive"))
      (node (ref "HL41") (pin "2") (pinfunction "2_2") (pintype "passive"))
      (node (ref "HL49") (pin "1") (pinfunction "1_1") (pintype "passive"))
      (node (ref "HL57") (pin "2") (pinfunction "2_2") (pintype "passive"))
      (node (ref "HL64") (pin "1") (pinfunction "1_1") (pintype "passive"))
      (node (ref "HL70") (pin "2") (pinfunction "2_2") (pintype "passive"))
      (node (ref "HL75") (pin "1") (pinfunction "1_1") (pintype "passive"))
      (node (ref "HL80") (pin "2") (pinfunction "2_2") (pintype "passive"))
      (node (ref "HL84") (pin "1") (pinfunction "1_1") (pintype "passive"))
      (node (ref "HL88") (pin "2") (pinfunction "2_2") (pintype "passive"))
      (node (ref "HL91") (pin "1") (pinfunction "1_1") (pintype "passive"))
      (node (ref "HL94") (pin "2") (pinfunction "2_2") (pintype "passive"))
      (node (ref "HL97") (pin "2") (pinfunction "2_2") (pintype "passive"))
      (node (ref "HL98") (pin "2") (pinfunction "2_2") (pintype "passive"))
      (node (ref "HL99") (pin "1") (pinfunction "1_1") (pintype "passive"))
      (node (ref "R42") (pin "1") (pinfunction "1_1") (pintype "passive"))
    )
    (net (code "20") (name "/ROW8") (class "Default")
      (node (ref "HL101") (pin "2") (pinfunction "2_2") (pintype "passive"))
      (node (ref "HL102") (pin "1") (pinfunction "1_1") (pintype "passive"))
      (node (ref "HL14") (pin "1") (pinfunction "1_1") (pintype "passive"))
      (node (ref "HL24") (pin "2") (pinfunction "2_2") (pintype "passive"))
      (node (ref "HL33") (pin "1") (pinfunction "1_1") (pintype "passive"))
      (node (ref "HL42") (pin "2") (pinfunction "2_2") (pintype "passive"))
      (node (ref "HL50") (pin "1") (pinfunction "1_1") (pintype "passive"))
      (node (ref "HL58") (pin "2") (pinfunction "2_2") (pintype "passive"))
      (node (ref "HL65") (pin "1") (pinfunction "1_1") (pintype "passive"))
      (node (ref "HL71") (pin "2") (pinfunction "2_2") (pintype "passive"))
      (node (ref "HL76") (pin "1") (pinfunction "1_1") (pintype "passive"))
      (node (ref "HL81") (pin "2") (pinfunction "2_2") (pintype "passive"))
      (node (ref "HL85") (pin "1") (pinfunction "1_1") (pintype "passive"))
      (node (ref "HL89") (pin "2") (pinfunction "2_2") (pintype "passive"))
      (node (ref "HL92") (pin "1") (pinfunction "1_1") (pintype "passive"))
      (node (ref "HL95") (pin "2") (pinfunction "2_2") (pintype "passive"))
      (node (ref "HL97") (pin "1") (pinfunction "1_1") (pintype "passive"))
      (node (ref "HL99") (pin "2") (pinfunction "2_2") (pintype "passive"))
      (node (ref "R43") (pin "1") (pinfunction "1_1") (pintype "passive"))
    )
    (net (code "21") (name "/ROW9") (class "Default")
      (node (ref "HL100") (pin "2") (pinfunction "2_2") (pintype "passive"))
      (node (ref "HL101") (pin "1") (pinfunction "1_1") (pintype "passive"))
      (node (ref "HL102") (pin "2") (pinfunction "2_2") (pintype "passive"))
      (node (ref "HL15") (pin "1") (pinfunction "1_1") (pintype "passive"))
      (node (ref "HL25") (pin "2") (pinfunction "2_2") (pintype "passive"))
      (node (ref "HL34") (pin "1") (pinfunction "1_1") (pintype "passive"))
      (node (ref "HL43") (pin "2") (pinfunction "2_2") (pintype "passive"))
      (node (ref "HL51") (pin "1") (pinfunction "1_1") (pintype "passive"))
      (node (ref "HL59") (pin "2") (pinfunction "2_2") (pintype "passive"))
      (node (ref "HL66") (pin "1") (pinfunction "1_1") (pintype "passive"))
      (node (ref "HL72") (pin "2") (pinfunction "2_2") (pintype "passive"))
      (node (ref "HL77") (pin "1") (pinfunction "1_1") (pintype "passive"))
      (node (ref "HL82") (pin "2") (pinfunction "2_2") (pintype "passive"))
      (node (ref "HL86") (pin "1") (pinfunction "1_1") (pintype "passive"))
      (node (ref "HL90") (pin "2") (pinfunction "2_2") (pintype "passive"))
      (node (ref "HL93") (pin "1") (pinfunction "1_1") (pintype "passive"))
      (node (ref "HL96") (pin "2") (pinfunction "2_2") (pintype "passive"))
      (node (ref "HL98") (pin "1") (pinfunction "1_1") (pintype "passive"))
      (node (ref "R44") (pin "1") (pinfunction "1_1") (pintype "passive"))
    )
    (net (code "22") (name "/ROW10") (class "Default")
      (node (ref "HL16") (pin "1") (pinfunction "1_1") (pintype "passive"))
      (node (ref "HL26") (pin "2") (pinfunction "2_2") (pintype "passive"))
      (node (ref "HL35") (pin "1") (pinfunction "1_1") (pintype "passive"))
      (node (ref "HL44") (pin "2") (pinfunction "2_2") (pintype "passive"))
      (node (ref "HL52") (pin "1") (pinfunction "1_1") (pintype "passive"))
      (node (ref "HL60") (pin "2") (pinfunction "2_2") (pintype "passive"))
      (node (ref "R45") (pin "1") (pinfunction "1_1") (pintype "passive"))
    )
  )
)
